# GZ7_1_x-POWER.net
KiCad netlist of a schematic drawn in Altium Designer
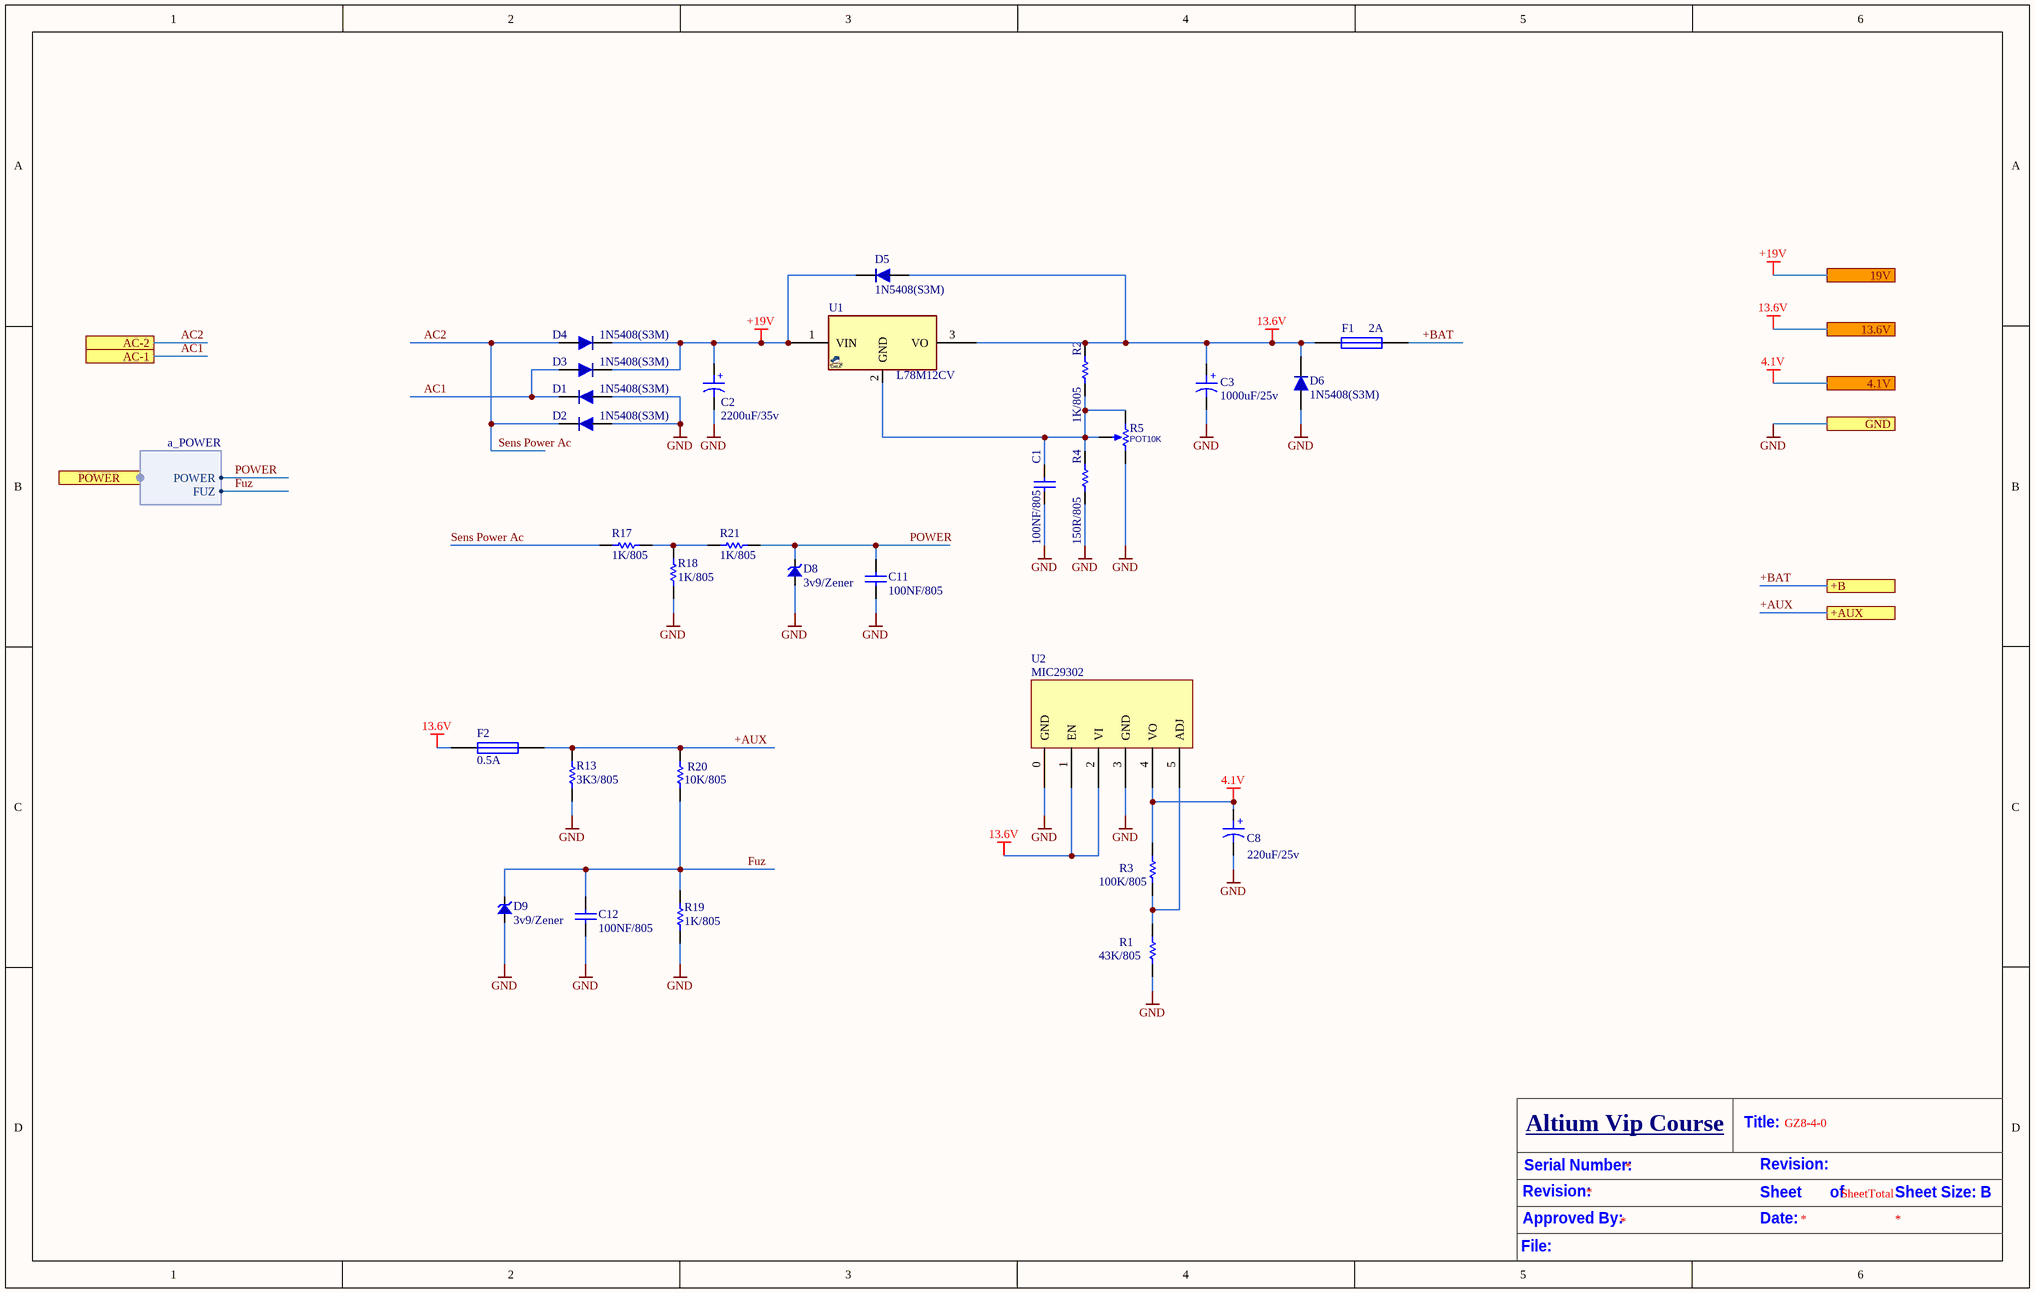
[diagram p0: GZ7_1_x-POWER.SchDoc]

(export (version "E")
  (design (tool "Eeschema 10.0.6"))
  (components
    (comp (ref "C1")
      (value "100NF/805")
      (footprint "MY805 COP")
      (description "CAP 0805")
      (fields (field (name "DESIGNER") "Abbas Basereh"))
      (libsource (lib "Altium") (part "CAP SMD 0805"))
    )
    (comp (ref "C2")
      (value "2200uF/35v")
      (footprint "C_EL_10X16")
      (description "Cap electrolitic radial")
      (fields (field (name "DESIGNER") "Abbas Basereh"))
      (libsource (lib "Altium") (part "Cap electrolitic radial 18x26"))
    )
    (comp (ref "C3")
      (value "1000uF/25v")
      (footprint "C_EL_10X16")
      (description "Cap electrolitic radial")
      (fields (field (name "DESIGNER") "Abbas Basereh"))
      (libsource (lib "Altium") (part "Cap electrolitic radial 18x26"))
    )
    (comp (ref "C8")
      (value "220uF/25v")
      (footprint "C_EL_8X14")
      (description "Cap electrolitic radial")
      (libsource (lib "Altium") (part "Cap electrolitic radial 10x21"))
    )
    (comp (ref "C11")
      (value "100NF/805")
      (footprint "MY805 COP")
      (description "CAP 0805")
      (fields (field (name "DESIGNER") "Abbas Basereh"))
      (libsource (lib "Altium") (part "CAP SMD 0805"))
    )
    (comp (ref "C12")
      (value "100NF/805")
      (footprint "MY805 COP")
      (description "CAP 0805")
      (fields (field (name "DESIGNER") "Abbas Basereh"))
      (libsource (lib "Altium") (part "CAP SMD 0805"))
    )
    (comp (ref "D1")
      (value "1N5408(S3M)")
      (footprint "DIOD_5408")
      (description "Diode")
      (fields (field (name "DESIGNER") "Abbas Basereh"))
      (libsource (lib "Altium") (part "1N5819"))
    )
    (comp (ref "D2")
      (value "1N5408(S3M)")
      (footprint "DIOD_5408")
      (description "Diode")
      (fields (field (name "DESIGNER") "Abbas Basereh"))
      (libsource (lib "Altium") (part "1N5819"))
    )
    (comp (ref "D3")
      (value "1N5408(S3M)")
      (footprint "DIOD_5408")
      (description "Diode")
      (fields (field (name "DESIGNER") "Abbas Basereh"))
      (libsource (lib "Altium") (part "1N5819"))
    )
    (comp (ref "D4")
      (value "1N5408(S3M)")
      (footprint "DIOD_5408")
      (description "Diode")
      (fields (field (name "DESIGNER") "Abbas Basereh"))
      (libsource (lib "Altium") (part "1N5819"))
    )
    (comp (ref "D5")
      (value "1N5408(S3M)")
      (footprint "DIOD_5408")
      (description "Diode")
      (fields (field (name "DESIGNER") "Abbas Basereh"))
      (libsource (lib "Altium") (part "1N5819"))
    )
    (comp (ref "D6")
      (value "1N5408(S3M)")
      (footprint "DIOD_5408")
      (description "Diode")
      (fields (field (name "DESIGNER") "Abbas Basereh"))
      (libsource (lib "Altium") (part "1N5819"))
    )
    (comp (ref "D8") (value "3v9/Zener") (footprint "my-DO5X.1.5") (libsource (lib "Ebrahim") (part "Zener")))
    (comp (ref "D9") (value "3v9/Zener") (footprint "my-DO5X.1.5") (libsource (lib "Ebrahim") (part "Zener")))
    (comp (ref "F1")
      (value "2A")
      (footprint "Fuse 5x20 With holder pin")
      (description "Fuse")
      (libsource (lib "*") (part "FUSE1"))
    )
    (comp (ref "F2")
      (value "0.5A")
      (footprint "Fuse 5x20 With holder pin")
      (description "Fuse")
      (libsource (lib "*") (part "FUSE1"))
    )
    (comp (ref "R1")
      (value "43K/805")
      (footprint "my805")
      (description "RES 805")
      (fields (field (name "DESIGNER") "Abbas Basereh"))
      (libsource (lib "Altium") (part "RES 1206 0.25W"))
    )
    (comp (ref "R2")
      (value "1K/805")
      (footprint "my805")
      (description "RES 805")
      (fields (field (name "DESIGNER") "Abbas Basereh"))
      (libsource (lib "Altium") (part "RES 1206 0.25W"))
    )
    (comp (ref "R3")
      (value "100K/805")
      (footprint "my805")
      (description "RES 805")
      (fields (field (name "DESIGNER") "Abbas Basereh"))
      (libsource (lib "Altium") (part "RES 1206 0.25W"))
    )
    (comp (ref "R4")
      (value "150R/805")
      (footprint "my805")
      (description "RES 805")
      (fields (field (name "DESIGNER") "Abbas Basereh"))
      (libsource (lib "Altium") (part "RES 1206 0.25W"))
    )
    (comp (ref "R5")
      (value "POT10K")
      (footprint "POT_7X5")
      (description "RESISTOR, THD, Potentiometer")
      (libsource (lib "resistor_pot_trimmer") (part "RES_THD_POT_7X5"))
    )
    (comp (ref "R13")
      (value "3K3/805")
      (footprint "my805")
      (description "RES 805")
      (fields (field (name "DESIGNER") "Abbas Basereh"))
      (libsource (lib "Altium") (part "RES 1206 0.25W"))
    )
    (comp (ref "R17")
      (value "1K/805")
      (footprint "my805")
      (description "RES 805")
      (fields (field (name "DESIGNER") "Abbas Basereh"))
      (libsource (lib "Altium") (part "RES 1206 0.25W"))
    )
    (comp (ref "R18")
      (value "1K/805")
      (footprint "my805")
      (description "RES 805")
      (fields (field (name "DESIGNER") "Abbas Basereh"))
      (libsource (lib "Altium") (part "RES 1206 0.25W"))
    )
    (comp (ref "R19")
      (value "1K/805")
      (footprint "my805")
      (description "RES 805")
      (fields (field (name "DESIGNER") "Abbas Basereh"))
      (libsource (lib "Altium") (part "RES 1206 0.25W"))
    )
    (comp (ref "R20")
      (value "10K/805")
      (footprint "my805")
      (description "RES 805")
      (fields (field (name "DESIGNER") "Abbas Basereh"))
      (libsource (lib "Altium") (part "RES 1206 0.25W"))
    )
    (comp (ref "R21")
      (value "1K/805")
      (footprint "my805")
      (description "RES 805")
      (fields (field (name "DESIGNER") "Abbas Basereh"))
      (libsource (lib "Altium") (part "RES 1206 0.25W"))
    )
    (comp (ref "U1")
      (value "L78M12CV")
      (footprint "HSINK_TO220E")
      (description "REG, Linear, Fixed, 12v, 1.5A, TO220")
      (fields (field (name "MANF_P#") "L78M12CV, MC78M12CTG, UA78M12CKC") (field (name "MANF") "TI, ST, ON"))
      (libsource (lib "pwr_reg_linear_78xx79xx") (part "VREG_78M12_TO220"))
    )
    (comp (ref "U2")
      (value "MIC29302")
      (footprint "my29302")
      (libsource (lib "MGZ8-V3") (part "Component_1_1"))
    )
  )
  (nets
    (net (code "2") (name "+19V") (class "Default")
      (node (ref "C2") (pin "1") (pinfunction "1_1") (pintype "passive"))
      (node (ref "D3") (pin "2") (pintype "passive"))
      (node (ref "D4") (pin "2") (pintype "passive"))
      (node (ref "D5") (pin "2") (pintype "passive"))
      (node (ref "U1") (pin "1") (pinfunction "VIN_1") (pintype "passive"))
    )
    (net (code "3") (name "/+AUX") (class "Default")
      (node (ref "F2") (pin "2") (pinfunction "2_2") (pintype "passive"))
      (node (ref "R13") (pin "2") (pinfunction "2_2") (pintype "passive"))
      (node (ref "R20") (pin "2") (pinfunction "2_2") (pintype "passive"))
    )
    (net (code "4") (name "/+BAT") (class "Default")
      (node (ref "F1") (pin "2") (pinfunction "2_2") (pintype "passive"))
    )
    (net (code "5") (name "/AC1") (class "Default")
      (node (ref "D1") (pin "2") (pintype "passive"))
      (node (ref "D3") (pin "1") (pintype "passive"))
    )
    (net (code "6") (name "/AC2") (class "Default")
      (node (ref "D2") (pin "2") (pintype "passive"))
      (node (ref "D4") (pin "1") (pintype "passive"))
      (node (ref "R17") (pin "1") (pinfunction "1_1") (pintype "passive"))
    )
    (net (code "7") (name "/Fuz") (class "Default")
      (node (ref "C12") (pin "2") (pinfunction "2_2") (pintype "passive"))
      (node (ref "D9") (pin "2") (pintype "passive"))
      (node (ref "R19") (pin "2") (pinfunction "2_2") (pintype "passive"))
      (node (ref "R20") (pin "1") (pinfunction "1_1") (pintype "passive"))
    )
    (net (code "8") (name "/POWER") (class "Default")
      (node (ref "C11") (pin "2") (pinfunction "2_2") (pintype "passive"))
      (node (ref "D8") (pin "2") (pintype "passive"))
      (node (ref "R21") (pin "2") (pinfunction "2_2") (pintype "passive"))
    )
    (net (code "10") (name "4.1V") (class "Default")
      (node (ref "C8") (pin "1") (pinfunction "1_1") (pintype "passive"))
      (node (ref "R3") (pin "2") (pinfunction "2_2") (pintype "passive"))
      (node (ref "U2") (pin "4") (pinfunction "VO_4") (pintype "passive"))
    )
    (net (code "11") (name "13.6V") (class "Default")
      (node (ref "C3") (pin "1") (pinfunction "1_1") (pintype "passive"))
      (node (ref "D5") (pin "1") (pintype "passive"))
      (node (ref "D6") (pin "2") (pintype "passive"))
      (node (ref "F1") (pin "1") (pinfunction "1_1") (pintype "passive"))
      (node (ref "F2") (pin "1") (pinfunction "1_1") (pintype "passive"))
      (node (ref "R2") (pin "2") (pinfunction "2_2") (pintype "passive"))
      (node (ref "U1") (pin "3") (pinfunction "VO_3") (pintype "passive"))
      (node (ref "U2") (pin "1") (pinfunction "EN_1") (pintype "passive"))
      (node (ref "U2") (pin "2") (pinfunction "VI_2") (pintype "passive"))
    )
    (net (code "12") (name "GND") (class "Default")
      (node (ref "C1") (pin "1") (pinfunction "1_1") (pintype "passive"))
      (node (ref "C11") (pin "1") (pinfunction "1_1") (pintype "passive"))
      (node (ref "C12") (pin "1") (pinfunction "1_1") (pintype "passive"))
      (node (ref "C2") (pin "2") (pinfunction "2_2") (pintype "passive"))
      (node (ref "C3") (pin "2") (pinfunction "2_2") (pintype "passive"))
      (node (ref "C8") (pin "2") (pinfunction "2_2") (pintype "passive"))
      (node (ref "D1") (pin "1") (pintype "passive"))
      (node (ref "D2") (pin "1") (pintype "passive"))
      (node (ref "D6") (pin "1") (pintype "passive"))
      (node (ref "D8") (pin "1") (pintype "passive"))
      (node (ref "D9") (pin "1") (pintype "passive"))
      (node (ref "R1") (pin "1") (pinfunction "1_1") (pintype "passive"))
      (node (ref "R13") (pin "1") (pinfunction "1_1") (pintype "passive"))
      (node (ref "R18") (pin "1") (pinfunction "1_1") (pintype "passive"))
      (node (ref "R19") (pin "1") (pinfunction "1_1") (pintype "passive"))
      (node (ref "R4") (pin "1") (pinfunction "1_1") (pintype "passive"))
      (node (ref "R5") (pin "3") (pinfunction "BOT_3") (pintype "passive"))
      (node (ref "U2") (pin "0") (pinfunction "GND_0") (pintype "passive"))
      (node (ref "U2") (pin "3") (pinfunction "GND_3") (pintype "passive"))
    )
    (net (code "13") (name "Net-(R5-TAP)") (class "Default")
      (node (ref "C1") (pin "2") (pinfunction "2_2") (pintype "passive"))
      (node (ref "R2") (pin "1") (pinfunction "1_1") (pintype "passive"))
      (node (ref "R4") (pin "2") (pinfunction "2_2") (pintype "passive"))
      (node (ref "R5") (pin "1") (pinfunction "TOP_1") (pintype "passive"))
      (node (ref "R5") (pin "2") (pinfunction "TAP_2") (pintype "passive"))
      (node (ref "U1") (pin "2") (pinfunction "GND_2") (pintype "passive"))
    )
    (net (code "14") (name "Net-(R17-Pad2)") (class "Default")
      (node (ref "R17") (pin "2") (pinfunction "2_2") (pintype "passive"))
      (node (ref "R18") (pin "2") (pinfunction "2_2") (pintype "passive"))
      (node (ref "R21") (pin "1") (pinfunction "1_1") (pintype "passive"))
    )
    (net (code "15") (name "Net-(U2-ADJ)") (class "Default")
      (node (ref "R1") (pin "2") (pinfunction "2_2") (pintype "passive"))
      (node (ref "R3") (pin "1") (pinfunction "1_1") (pintype "passive"))
      (node (ref "U2") (pin "5") (pinfunction "ADJ_5") (pintype "passive"))
    )
  )
)
